# protestSignNode.net
KiCad netlist of a schematic drawn in EAGLE
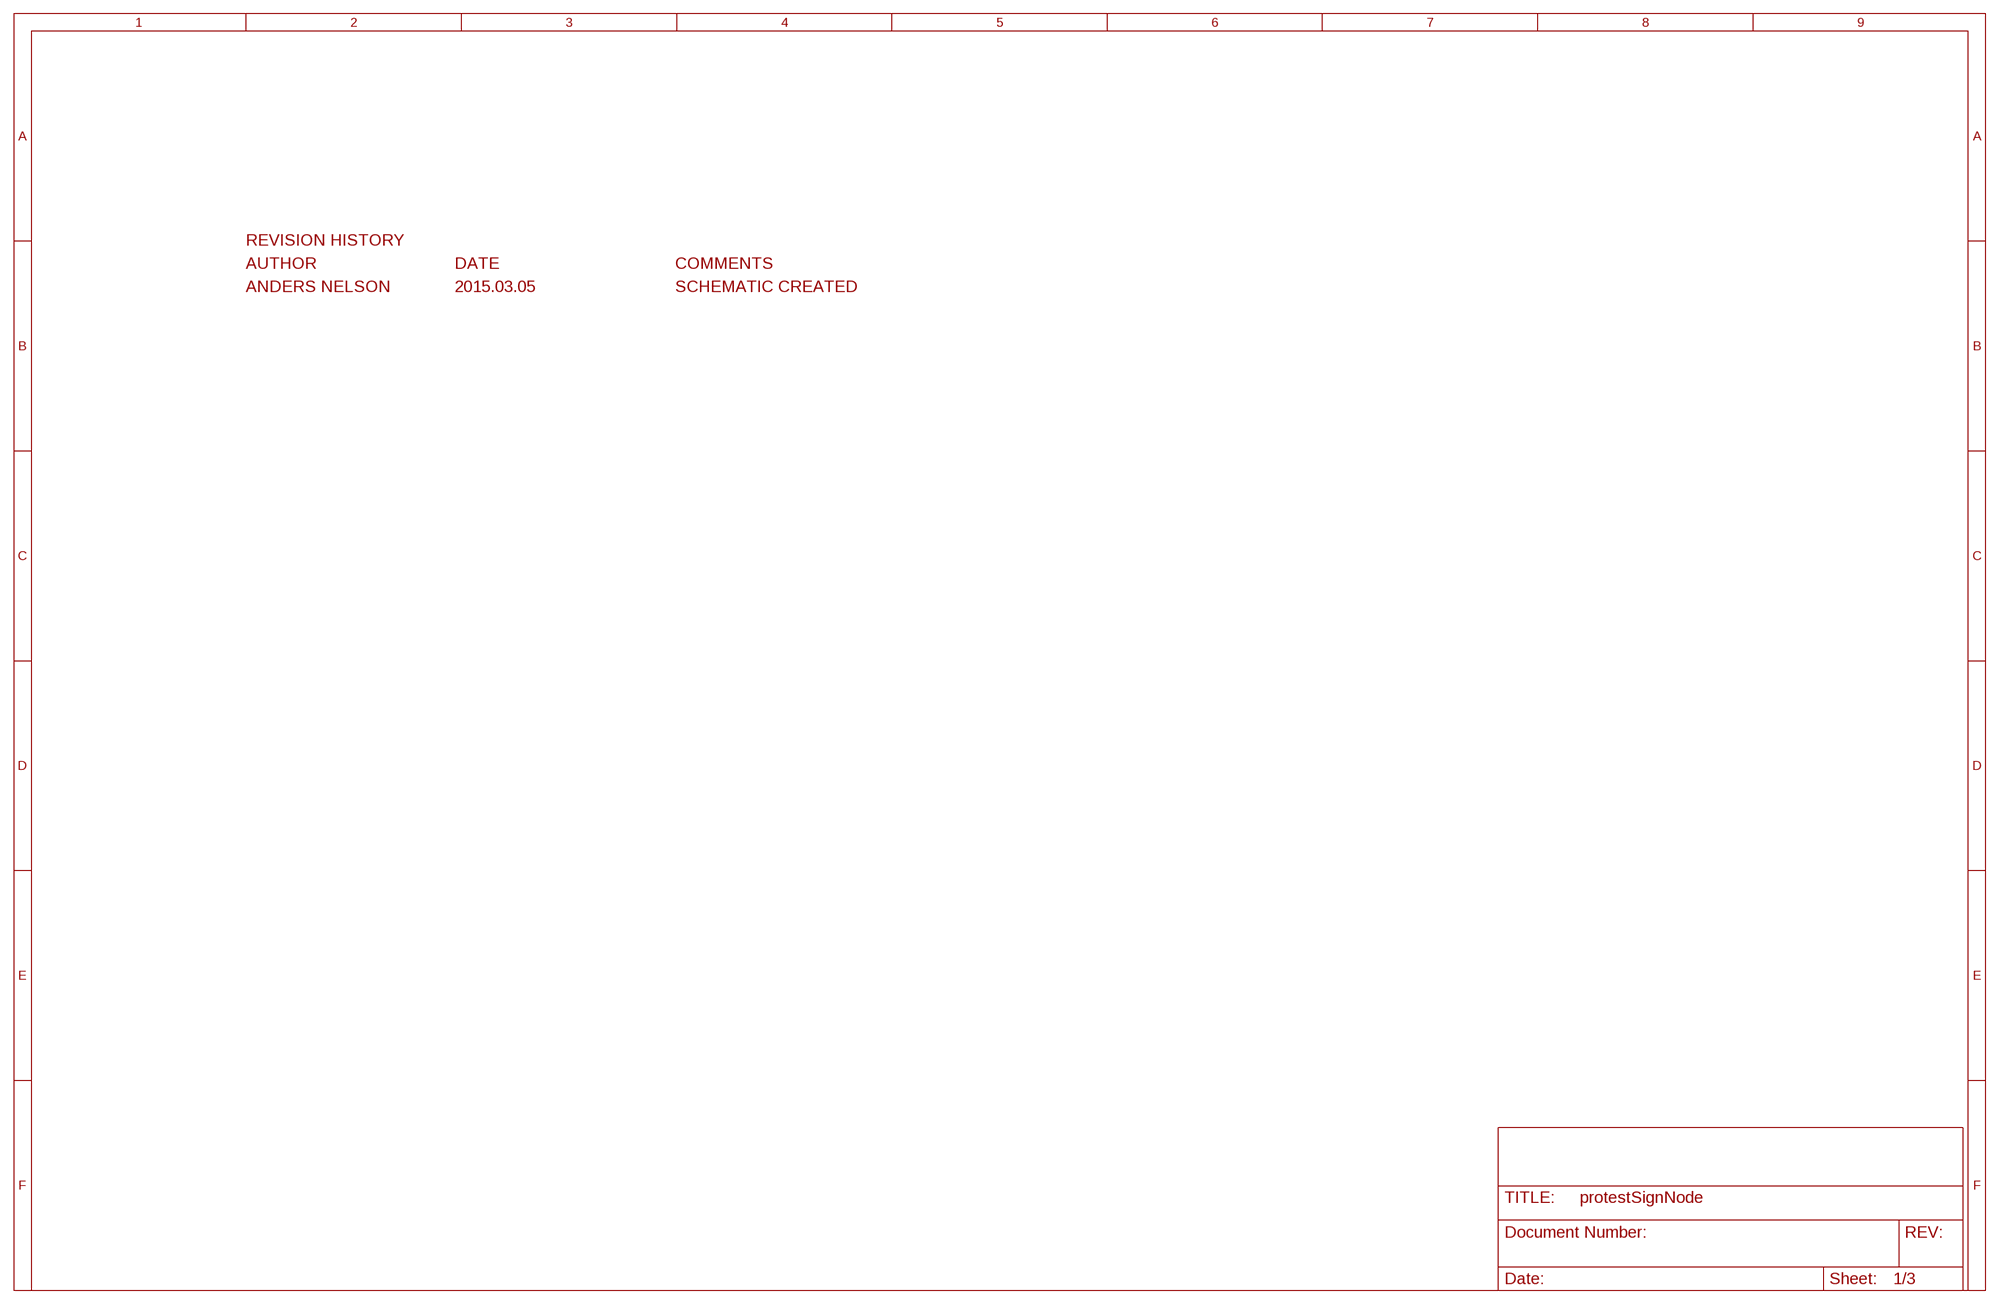
[diagram p0: schematic, sheet 1]
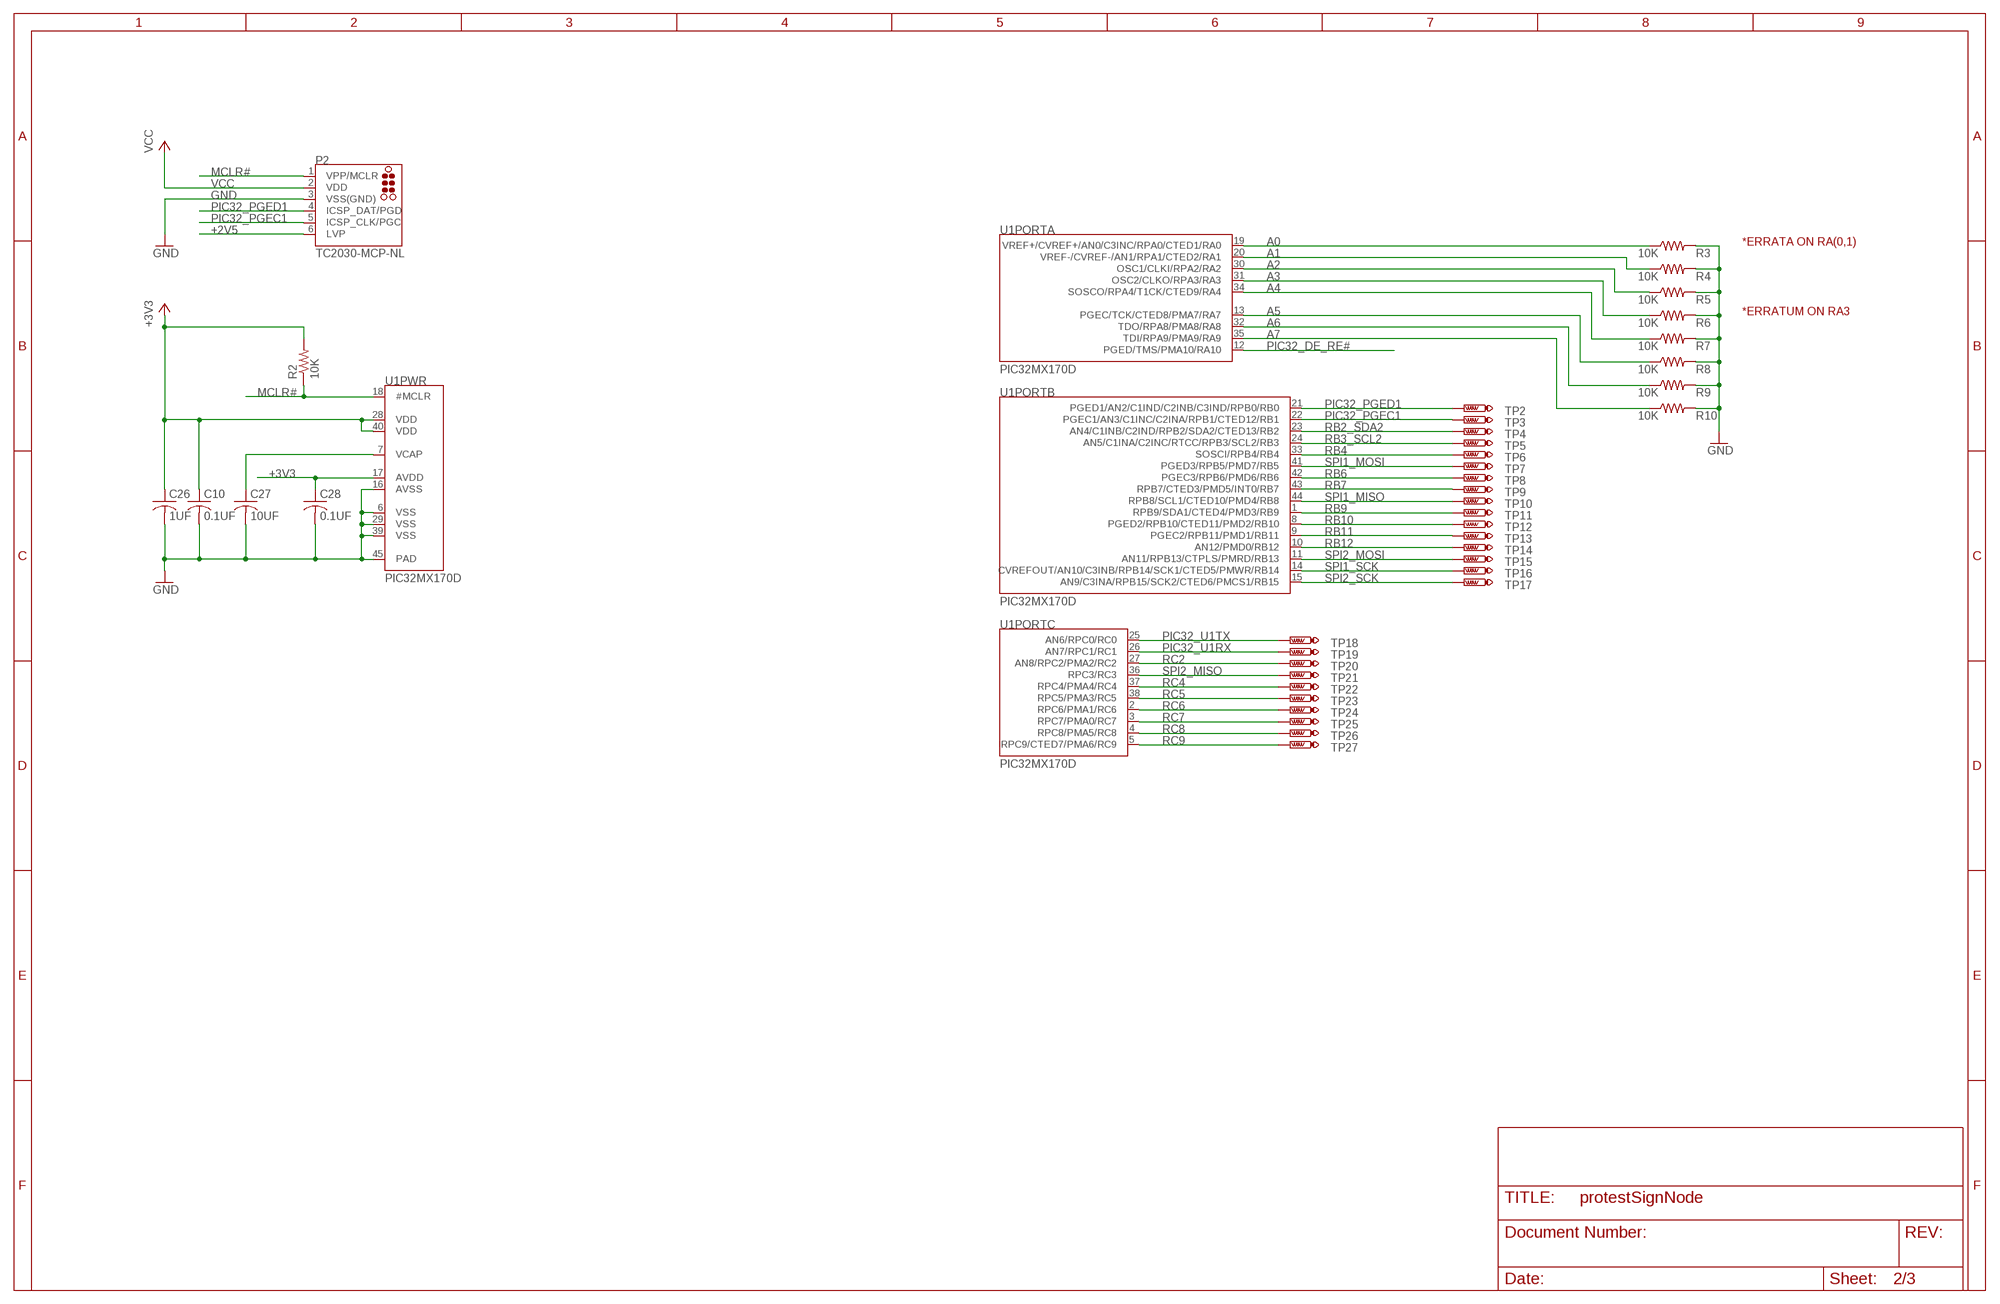
[diagram p1: schematic, sheet 2]
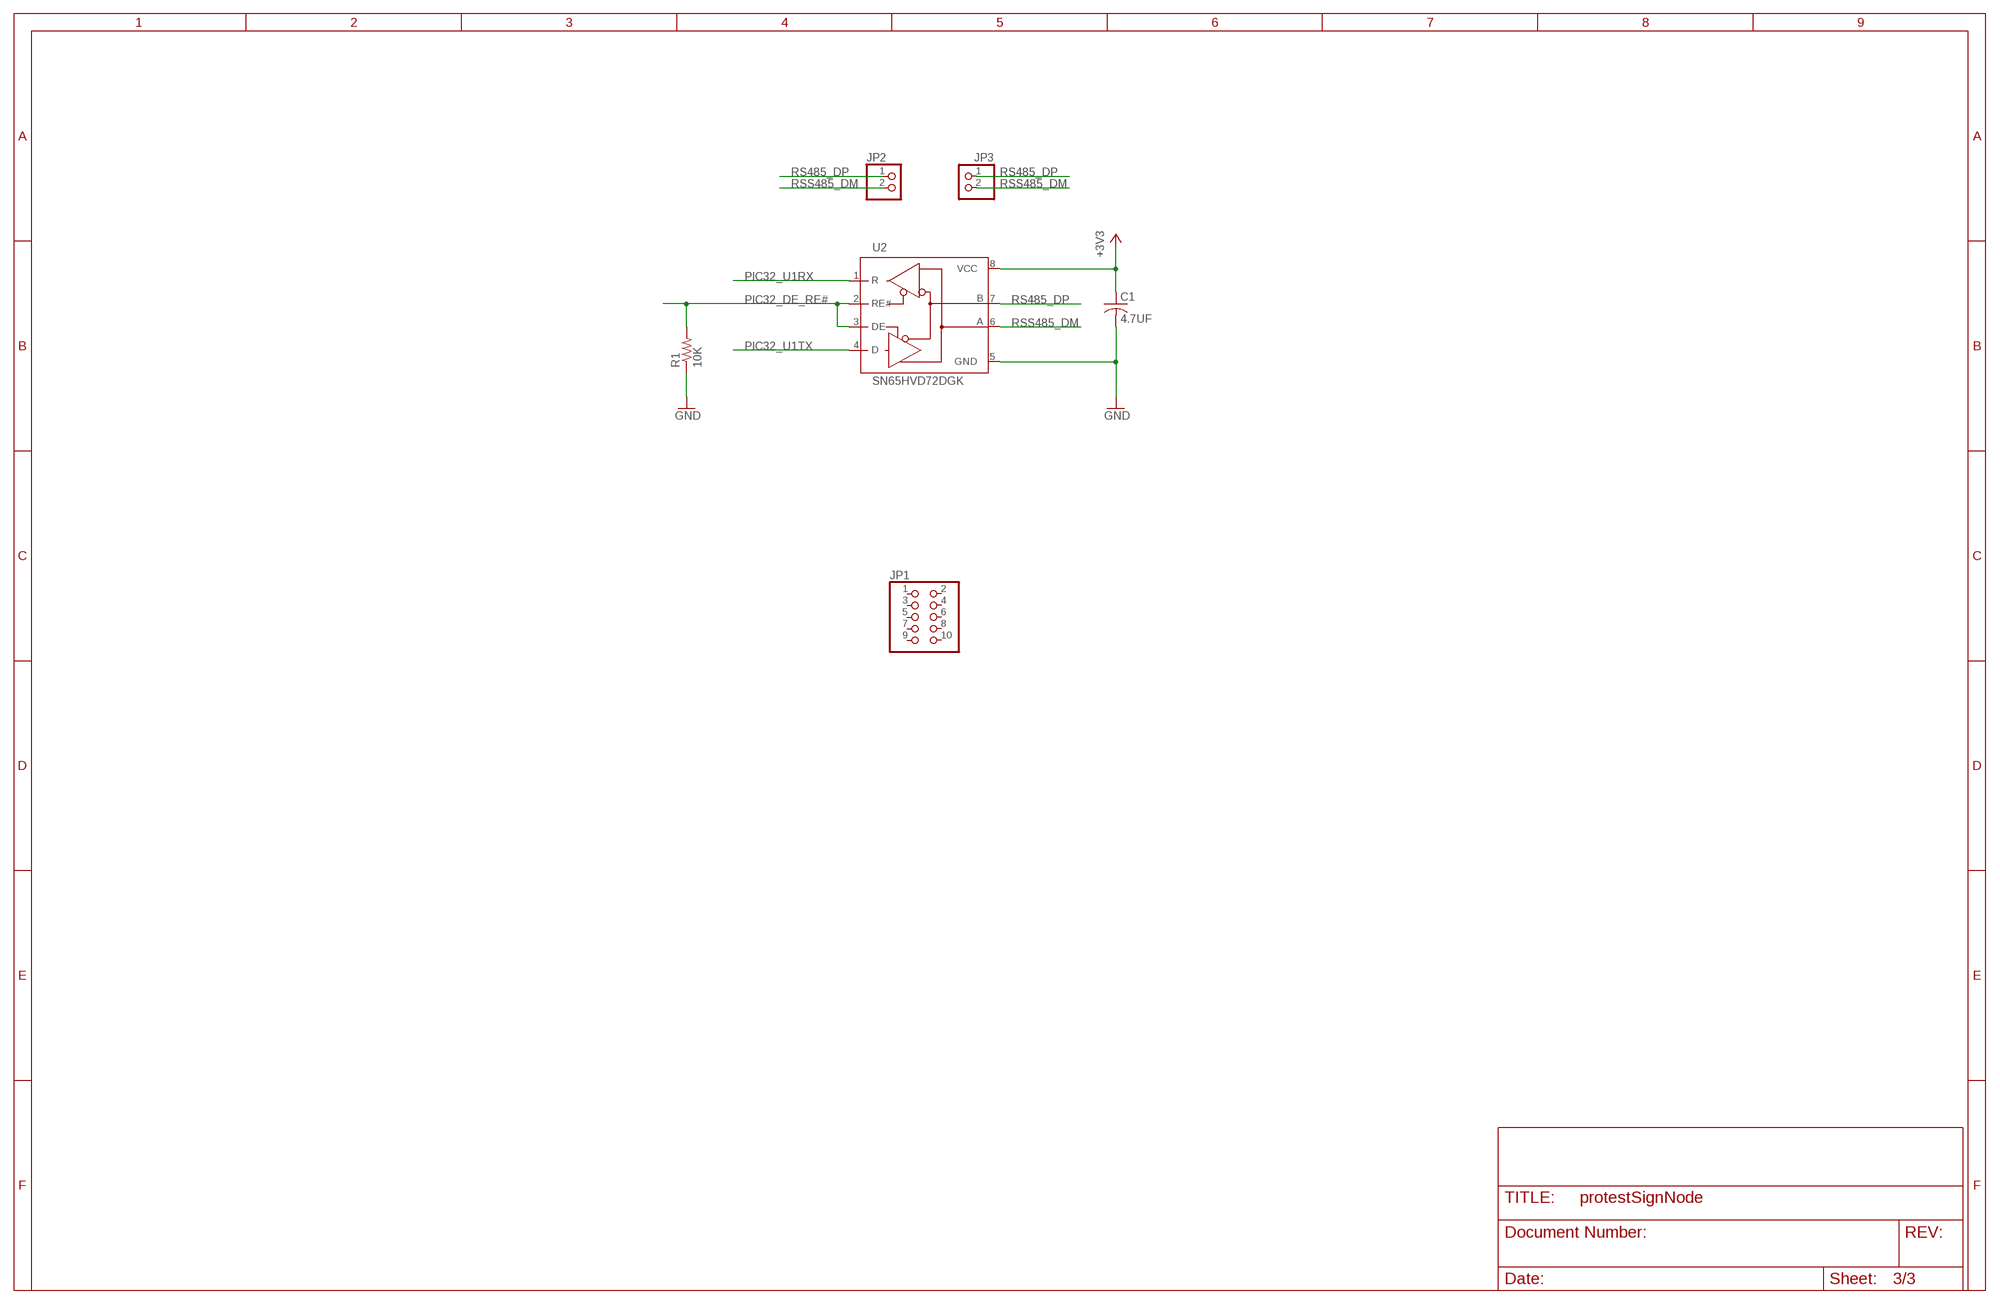
[diagram p2: schematic, sheet 3]

(export (version "E")
  (design (tool "Eeschema 10.0.6"))
  (components
    (comp (ref "C10")
      (value "0.1UF")
      (footprint "eagle-import:C0402")
      (libsource (lib "eagle-import") (part "C-USC0402"))
    )
    (comp (ref "C26")
      (value "1UF")
      (footprint "eagle-import:C0402")
      (libsource (lib "eagle-import") (part "C-USC0402"))
    )
    (comp (ref "C27")
      (value "10UF")
      (footprint "eagle-import:C0603")
      (libsource (lib "eagle-import") (part "C-USC0603"))
    )
    (comp (ref "C28")
      (value "0.1UF")
      (footprint "eagle-import:C0402")
      (libsource (lib "eagle-import") (part "C-USC0402"))
    )
    (comp (ref "P2")
      (value "TC2030-MCP-NL")
      (footprint "eagle-import:TC2030-MCP-NL")
      (libsource (lib "eagle-import") (part "TC2030-MCP-NL"))
    )
    (comp (ref "R2")
      (value "10K")
      (footprint "eagle-import:R0402")
      (libsource (lib "eagle-import") (part "R-US_R0402"))
    )
    (comp (ref "R3")
      (value "10K")
      (footprint "eagle-import:R0402")
      (libsource (lib "eagle-import") (part "R-US_R0402"))
    )
    (comp (ref "R4")
      (value "10K")
      (footprint "eagle-import:R0402")
      (libsource (lib "eagle-import") (part "R-US_R0402"))
    )
    (comp (ref "R5")
      (value "10K")
      (footprint "eagle-import:R0402")
      (libsource (lib "eagle-import") (part "R-US_R0402"))
    )
    (comp (ref "R6")
      (value "10K")
      (footprint "eagle-import:R0402")
      (libsource (lib "eagle-import") (part "R-US_R0402"))
    )
    (comp (ref "R7")
      (value "10K")
      (footprint "eagle-import:R0402")
      (libsource (lib "eagle-import") (part "R-US_R0402"))
    )
    (comp (ref "R8")
      (value "10K")
      (footprint "eagle-import:R0402")
      (libsource (lib "eagle-import") (part "R-US_R0402"))
    )
    (comp (ref "R9")
      (value "10K")
      (footprint "eagle-import:R0402")
      (libsource (lib "eagle-import") (part "R-US_R0402"))
    )
    (comp (ref "R10")
      (value "10K")
      (footprint "eagle-import:R0402")
      (libsource (lib "eagle-import") (part "R-US_R0402"))
    )
    (comp (ref "TP2")
      (value "PTR1B1,27")
      (footprint "eagle-import:B1,27")
      (libsource (lib "eagle-import") (part "PTR1B1,27"))
    )
    (comp (ref "TP3")
      (value "PTR1B1,27")
      (footprint "eagle-import:B1,27")
      (libsource (lib "eagle-import") (part "PTR1B1,27"))
    )
    (comp (ref "TP4")
      (value "PTR1B1,27")
      (footprint "eagle-import:B1,27")
      (libsource (lib "eagle-import") (part "PTR1B1,27"))
    )
    (comp (ref "TP5")
      (value "PTR1B1,27")
      (footprint "eagle-import:B1,27")
      (libsource (lib "eagle-import") (part "PTR1B1,27"))
    )
    (comp (ref "TP6")
      (value "PTR1B1,27")
      (footprint "eagle-import:B1,27")
      (libsource (lib "eagle-import") (part "PTR1B1,27"))
    )
    (comp (ref "TP7")
      (value "PTR1B1,27")
      (footprint "eagle-import:B1,27")
      (libsource (lib "eagle-import") (part "PTR1B1,27"))
    )
    (comp (ref "TP8")
      (value "PTR1B1,27")
      (footprint "eagle-import:B1,27")
      (libsource (lib "eagle-import") (part "PTR1B1,27"))
    )
    (comp (ref "TP9")
      (value "PTR1B1,27")
      (footprint "eagle-import:B1,27")
      (libsource (lib "eagle-import") (part "PTR1B1,27"))
    )
    (comp (ref "TP10")
      (value "PTR1B1,27")
      (footprint "eagle-import:B1,27")
      (libsource (lib "eagle-import") (part "PTR1B1,27"))
    )
    (comp (ref "TP11")
      (value "PTR1B1,27")
      (footprint "eagle-import:B1,27")
      (libsource (lib "eagle-import") (part "PTR1B1,27"))
    )
    (comp (ref "TP12")
      (value "PTR1B1,27")
      (footprint "eagle-import:B1,27")
      (libsource (lib "eagle-import") (part "PTR1B1,27"))
    )
    (comp (ref "TP13")
      (value "PTR1B1,27")
      (footprint "eagle-import:B1,27")
      (libsource (lib "eagle-import") (part "PTR1B1,27"))
    )
    (comp (ref "TP14")
      (value "PTR1B1,27")
      (footprint "eagle-import:B1,27")
      (libsource (lib "eagle-import") (part "PTR1B1,27"))
    )
    (comp (ref "TP15")
      (value "PTR1B1,27")
      (footprint "eagle-import:B1,27")
      (libsource (lib "eagle-import") (part "PTR1B1,27"))
    )
    (comp (ref "TP16")
      (value "PTR1B1,27")
      (footprint "eagle-import:B1,27")
      (libsource (lib "eagle-import") (part "PTR1B1,27"))
    )
    (comp (ref "TP17")
      (value "PTR1B1,27")
      (footprint "eagle-import:B1,27")
      (libsource (lib "eagle-import") (part "PTR1B1,27"))
    )
    (comp (ref "TP18")
      (value "PTR1B1,27")
      (footprint "eagle-import:B1,27")
      (libsource (lib "eagle-import") (part "PTR1B1,27"))
    )
    (comp (ref "TP19")
      (value "PTR1B1,27")
      (footprint "eagle-import:B1,27")
      (libsource (lib "eagle-import") (part "PTR1B1,27"))
    )
    (comp (ref "TP20")
      (value "PTR1B1,27")
      (footprint "eagle-import:B1,27")
      (libsource (lib "eagle-import") (part "PTR1B1,27"))
    )
    (comp (ref "TP21")
      (value "PTR1B1,27")
      (footprint "eagle-import:B1,27")
      (libsource (lib "eagle-import") (part "PTR1B1,27"))
    )
    (comp (ref "TP22")
      (value "PTR1B1,27")
      (footprint "eagle-import:B1,27")
      (libsource (lib "eagle-import") (part "PTR1B1,27"))
    )
    (comp (ref "TP23")
      (value "PTR1B1,27")
      (footprint "eagle-import:B1,27")
      (libsource (lib "eagle-import") (part "PTR1B1,27"))
    )
    (comp (ref "TP24")
      (value "PTR1B1,27")
      (footprint "eagle-import:B1,27")
      (libsource (lib "eagle-import") (part "PTR1B1,27"))
    )
    (comp (ref "TP25")
      (value "PTR1B1,27")
      (footprint "eagle-import:B1,27")
      (libsource (lib "eagle-import") (part "PTR1B1,27"))
    )
    (comp (ref "TP26")
      (value "PTR1B1,27")
      (footprint "eagle-import:B1,27")
      (libsource (lib "eagle-import") (part "PTR1B1,27"))
    )
    (comp (ref "TP27")
      (value "PTR1B1,27")
      (footprint "eagle-import:B1,27")
      (libsource (lib "eagle-import") (part "PTR1B1,27"))
    )
    (comp (ref "U1")
      (value "PIC32MX170D")
      (footprint "eagle-import:VTLA44")
      (libsource (lib "eagle-import") (part "PIC32MX1D70"))
    )
    (comp (ref "C1")
      (value "4.7UF")
      (footprint "eagle-import:C0603")
      (libsource (lib "eagle-import") (part "C-USC0603"))
    )
    (comp (ref "JP1")
      (value "PINHD-2X5")
      (footprint "eagle-import:2X05")
      (libsource (lib "eagle-import") (part "PINHD-2X5"))
    )
    (comp (ref "JP2")
      (value "PINHD-1X2/90")
      (footprint "eagle-import:1X02_90")
      (libsource (lib "eagle-import") (part "PINHD-1X2/90"))
    )
    (comp (ref "JP3")
      (value "PINHD-1X2/90")
      (footprint "eagle-import:1X02_90")
      (libsource (lib "eagle-import") (part "PINHD-1X2/90"))
    )
    (comp (ref "R1")
      (value "10K")
      (footprint "eagle-import:R0402")
      (libsource (lib "eagle-import") (part "R-US_R0402"))
    )
    (comp (ref "U2")
      (value "SN65HVD72DGK")
      (footprint "eagle-import:DGK")
      (libsource (lib "eagle-import") (part "SN65HVD7DGK2"))
    )
  )
  (nets
    (net (code "1") (name "+2V5") (class "Default")
      (node (ref "P2") (pin "6") (pinfunction "LVP_6") (pintype "bidirectional"))
    )
    (net (code "2") (name "+3V3") (class "Default")
      (node (ref "C1") (pin "1") (pinfunction "1_1") (pintype "passive"))
      (node (ref "C10") (pin "1") (pinfunction "1_1") (pintype "passive"))
      (node (ref "C26") (pin "1") (pinfunction "1_1") (pintype "passive"))
      (node (ref "C28") (pin "1") (pinfunction "1_1") (pintype "passive"))
      (node (ref "R2") (pin "2") (pinfunction "2_2") (pintype "passive"))
      (node (ref "U1") (pin "17") (pinfunction "AVDD_17") (pintype "bidirectional"))
      (node (ref "U1") (pin "28") (pinfunction "VDD_28") (pintype "bidirectional"))
      (node (ref "U1") (pin "40") (pinfunction "VDD_40") (pintype "bidirectional"))
      (node (ref "U2") (pin "8") (pinfunction "VCC_8") (pintype "power_in"))
    )
    (net (code "3") (name "A0") (class "Default")
      (node (ref "R3") (pin "1") (pinfunction "1_1") (pintype "passive"))
      (node (ref "U1") (pin "19") (pinfunction "VREF+/CVREF+/AN0/C3INC/RPA0/CTED1/RA0_19") (pintype "bidirectional"))
    )
    (net (code "4") (name "A1") (class "Default")
      (node (ref "R4") (pin "1") (pinfunction "1_1") (pintype "passive"))
      (node (ref "U1") (pin "20") (pinfunction "VREF-/CVREF-/AN1/RPA1/CTED2/RA1_20") (pintype "bidirectional"))
    )
    (net (code "5") (name "A2") (class "Default")
      (node (ref "R5") (pin "1") (pinfunction "1_1") (pintype "passive"))
      (node (ref "U1") (pin "30") (pinfunction "OSC1/CLKI/RPA2/RA2_30") (pintype "bidirectional"))
    )
    (net (code "6") (name "A3") (class "Default")
      (node (ref "R6") (pin "1") (pinfunction "1_1") (pintype "passive"))
      (node (ref "U1") (pin "31") (pinfunction "OSC2/CLKO/RPA3/RA3_31") (pintype "bidirectional"))
    )
    (net (code "7") (name "A4") (class "Default")
      (node (ref "R7") (pin "1") (pinfunction "1_1") (pintype "passive"))
      (node (ref "U1") (pin "34") (pinfunction "SOSCO/RPA4/T1CK/CTED9/RA4_34") (pintype "bidirectional"))
    )
    (net (code "8") (name "A5") (class "Default")
      (node (ref "R8") (pin "1") (pinfunction "1_1") (pintype "passive"))
      (node (ref "U1") (pin "13") (pinfunction "PGEC/TCK/CTED8/PMA7/RA7_13") (pintype "bidirectional"))
    )
    (net (code "9") (name "A6") (class "Default")
      (node (ref "R9") (pin "1") (pinfunction "1_1") (pintype "passive"))
      (node (ref "U1") (pin "32") (pinfunction "TDO/RPA8/PMA8/RA8_32") (pintype "bidirectional"))
    )
    (net (code "10") (name "A7") (class "Default")
      (node (ref "R10") (pin "1") (pinfunction "1_1") (pintype "passive"))
      (node (ref "U1") (pin "35") (pinfunction "TDI/RPA9/PMA9/RA9_35") (pintype "bidirectional"))
    )
    (net (code "11") (name "GND") (class "Default")
      (node (ref "C1") (pin "2") (pinfunction "2_2") (pintype "passive"))
      (node (ref "C10") (pin "2") (pinfunction "2_2") (pintype "passive"))
      (node (ref "C26") (pin "2") (pinfunction "2_2") (pintype "passive"))
      (node (ref "C27") (pin "2") (pinfunction "2_2") (pintype "passive"))
      (node (ref "C28") (pin "2") (pinfunction "2_2") (pintype "passive"))
      (node (ref "P2") (pin "3") (pinfunction "VSS(GND)_3") (pintype "power_in"))
      (node (ref "R1") (pin "1") (pinfunction "1_1") (pintype "passive"))
      (node (ref "R10") (pin "2") (pinfunction "2_2") (pintype "passive"))
      (node (ref "R3") (pin "2") (pinfunction "2_2") (pintype "passive"))
      (node (ref "R4") (pin "2") (pinfunction "2_2") (pintype "passive"))
      (node (ref "R5") (pin "2") (pinfunction "2_2") (pintype "passive"))
      (node (ref "R6") (pin "2") (pinfunction "2_2") (pintype "passive"))
      (node (ref "R7") (pin "2") (pinfunction "2_2") (pintype "passive"))
      (node (ref "R8") (pin "2") (pinfunction "2_2") (pintype "passive"))
      (node (ref "R9") (pin "2") (pinfunction "2_2") (pintype "passive"))
      (node (ref "U1") (pin "16") (pinfunction "AVSS_16") (pintype "bidirectional"))
      (node (ref "U1") (pin "29") (pinfunction "VSS_29") (pintype "bidirectional"))
      (node (ref "U1") (pin "39") (pinfunction "VSS_39") (pintype "bidirectional"))
      (node (ref "U1") (pin "45") (pinfunction "PAD_45") (pintype "bidirectional"))
      (node (ref "U1") (pin "6") (pinfunction "VSS_6") (pintype "bidirectional"))
      (node (ref "U2") (pin "5") (pinfunction "GND_5") (pintype "power_in"))
    )
    (net (code "12") (name "MCLR#") (class "Default")
      (node (ref "P2") (pin "1") (pinfunction "VPP/MCLR_1") (pintype "passive"))
      (node (ref "R2") (pin "1") (pinfunction "1_1") (pintype "passive"))
      (node (ref "U1") (pin "18") (pinfunction "#MCLR_18") (pintype "bidirectional"))
    )
    (net (code "13") (name "Net-(U1D-VCAP)") (class "Default")
      (node (ref "C27") (pin "1") (pinfunction "1_1") (pintype "passive"))
      (node (ref "U1") (pin "7") (pinfunction "VCAP_7") (pintype "bidirectional"))
    )
    (net (code "14") (name "PIC32_DE_RE#") (class "Default")
      (node (ref "R1") (pin "2") (pinfunction "2_2") (pintype "passive"))
      (node (ref "U1") (pin "12") (pinfunction "PGED/TMS/PMA10/RA10_12") (pintype "bidirectional"))
      (node (ref "U2") (pin "2") (pinfunction "RE#_2") (pintype "input"))
      (node (ref "U2") (pin "3") (pinfunction "DE_3") (pintype "input"))
    )
    (net (code "15") (name "PIC32_PGEC1") (class "Default")
      (node (ref "P2") (pin "5") (pinfunction "ICSP_CLK/PGC_5") (pintype "output"))
      (node (ref "TP3") (pin "TP") (pinfunction "TP_TP") (pintype "input"))
      (node (ref "U1") (pin "22") (pinfunction "PGEC1/AN3/C1INC/C2INA/RPB1/CTED12/RB1_22") (pintype "bidirectional"))
    )
    (net (code "16") (name "PIC32_PGED1") (class "Default")
      (node (ref "P2") (pin "4") (pinfunction "ICSP_DAT/PGD_4") (pintype "bidirectional"))
      (node (ref "TP2") (pin "TP") (pinfunction "TP_TP") (pintype "input"))
      (node (ref "U1") (pin "21") (pinfunction "PGED1/AN2/C1IND/C2INB/C3IND/RPB0/RB0_21") (pintype "bidirectional"))
    )
    (net (code "17") (name "PIC32_U1RX") (class "Default")
      (node (ref "TP19") (pin "TP") (pinfunction "TP_TP") (pintype "input"))
      (node (ref "U1") (pin "26") (pinfunction "AN7/RPC1/RC1_26") (pintype "bidirectional"))
      (node (ref "U2") (pin "1") (pinfunction "R_1") (pintype "output"))
    )
    (net (code "18") (name "PIC32_U1TX") (class "Default")
      (node (ref "TP18") (pin "TP") (pinfunction "TP_TP") (pintype "input"))
      (node (ref "U1") (pin "25") (pinfunction "AN6/RPC0/RC0_25") (pintype "bidirectional"))
      (node (ref "U2") (pin "4") (pinfunction "D_4") (pintype "input"))
    )
    (net (code "19") (name "RB2_SDA2") (class "Default")
      (node (ref "TP4") (pin "TP") (pinfunction "TP_TP") (pintype "input"))
      (node (ref "U1") (pin "23") (pinfunction "AN4/C1INB/C2IND/RPB2/SDA2/CTED13/RB2_23") (pintype "bidirectional"))
    )
    (net (code "20") (name "RB3_SCL2") (class "Default")
      (node (ref "TP5") (pin "TP") (pinfunction "TP_TP") (pintype "input"))
      (node (ref "U1") (pin "24") (pinfunction "AN5/C1INA/C2INC/RTCC/RPB3/SCL2/RB3_24") (pintype "bidirectional"))
    )
    (net (code "21") (name "RB4") (class "Default")
      (node (ref "TP6") (pin "TP") (pinfunction "TP_TP") (pintype "input"))
      (node (ref "U1") (pin "33") (pinfunction "SOSCI/RPB4/RB4_33") (pintype "bidirectional"))
    )
    (net (code "22") (name "RB6") (class "Default")
      (node (ref "TP8") (pin "TP") (pinfunction "TP_TP") (pintype "input"))
      (node (ref "U1") (pin "42") (pinfunction "PGEC3/RPB6/PMD6/RB6_42") (pintype "bidirectional"))
    )
    (net (code "23") (name "RB7") (class "Default")
      (node (ref "TP9") (pin "TP") (pinfunction "TP_TP") (pintype "input"))
      (node (ref "U1") (pin "43") (pinfunction "RPB7/CTED3/PMD5/INT0/RB7_43") (pintype "bidirectional"))
    )
    (net (code "24") (name "RB9") (class "Default")
      (node (ref "TP11") (pin "TP") (pinfunction "TP_TP") (pintype "input"))
      (node (ref "U1") (pin "1") (pinfunction "RPB9/SDA1/CTED4/PMD3/RB9_1") (pintype "bidirectional"))
    )
    (net (code "25") (name "RB10") (class "Default")
      (node (ref "TP12") (pin "TP") (pinfunction "TP_TP") (pintype "input"))
      (node (ref "U1") (pin "8") (pinfunction "PGED2/RPB10/CTED11/PMD2/RB10_8") (pintype "bidirectional"))
    )
    (net (code "26") (name "RB11") (class "Default")
      (node (ref "TP13") (pin "TP") (pinfunction "TP_TP") (pintype "input"))
      (node (ref "U1") (pin "9") (pinfunction "PGEC2/RPB11/PMD1/RB11_9") (pintype "bidirectional"))
    )
    (net (code "27") (name "RB12") (class "Default")
      (node (ref "TP14") (pin "TP") (pinfunction "TP_TP") (pintype "input"))
      (node (ref "U1") (pin "10") (pinfunction "AN12/PMD0/RB12_10") (pintype "bidirectional"))
    )
    (net (code "28") (name "RC2") (class "Default")
      (node (ref "TP20") (pin "TP") (pinfunction "TP_TP") (pintype "input"))
      (node (ref "U1") (pin "27") (pinfunction "AN8/RPC2/PMA2/RC2_27") (pintype "bidirectional"))
    )
    (net (code "29") (name "RC4") (class "Default")
      (node (ref "TP22") (pin "TP") (pinfunction "TP_TP") (pintype "input"))
      (node (ref "U1") (pin "37") (pinfunction "RPC4/PMA4/RC4_37") (pintype "bidirectional"))
    )
    (net (code "30") (name "RC5") (class "Default")
      (node (ref "TP23") (pin "TP") (pinfunction "TP_TP") (pintype "input"))
      (node (ref "U1") (pin "38") (pinfunction "RPC5/PMA3/RC5_38") (pintype "bidirectional"))
    )
    (net (code "31") (name "RC6") (class "Default")
      (node (ref "TP24") (pin "TP") (pinfunction "TP_TP") (pintype "input"))
      (node (ref "U1") (pin "2") (pinfunction "RPC6/PMA1/RC6_2") (pintype "bidirectional"))
    )
    (net (code "32") (name "RC7") (class "Default")
      (node (ref "TP25") (pin "TP") (pinfunction "TP_TP") (pintype "input"))
      (node (ref "U1") (pin "3") (pinfunction "RPC7/PMA0/RC7_3") (pintype "bidirectional"))
    )
    (net (code "33") (name "RC8") (class "Default")
      (node (ref "TP26") (pin "TP") (pinfunction "TP_TP") (pintype "input"))
      (node (ref "U1") (pin "4") (pinfunction "RPC8/PMA5/RC8_4") (pintype "bidirectional"))
    )
    (net (code "34") (name "RC9") (class "Default")
      (node (ref "TP27") (pin "TP") (pinfunction "TP_TP") (pintype "input"))
      (node (ref "U1") (pin "5") (pinfunction "RPC9/CTED7/PMA6/RC9_5") (pintype "bidirectional"))
    )
    (net (code "35") (name "RS485_DP") (class "Default")
      (node (ref "JP2") (pin "1") (pinfunction "1_1") (pintype "passive"))
      (node (ref "JP3") (pin "1") (pinfunction "1_1") (pintype "passive"))
      (node (ref "U2") (pin "7") (pinfunction "B_7") (pintype "passive"))
    )
    (net (code "36") (name "RSS485_DM") (class "Default")
      (node (ref "JP2") (pin "2") (pinfunction "2_2") (pintype "passive"))
      (node (ref "JP3") (pin "2") (pinfunction "2_2") (pintype "passive"))
      (node (ref "U2") (pin "6") (pinfunction "A_6") (pintype "passive"))
    )
    (net (code "37") (name "SPI1_MISO") (class "Default")
      (node (ref "TP10") (pin "TP") (pinfunction "TP_TP") (pintype "input"))
      (node (ref "U1") (pin "44") (pinfunction "RPB8/SCL1/CTED10/PMD4/RB8_44") (pintype "bidirectional"))
    )
    (net (code "38") (name "SPI1_MOSI") (class "Default")
      (node (ref "TP7") (pin "TP") (pinfunction "TP_TP") (pintype "input"))
      (node (ref "U1") (pin "41") (pinfunction "PGED3/RPB5/PMD7/RB5_41") (pintype "bidirectional"))
    )
    (net (code "39") (name "SPI1_SCK") (class "Default")
      (node (ref "TP16") (pin "TP") (pinfunction "TP_TP") (pintype "input"))
      (node (ref "U1") (pin "14") (pinfunction "CVREFOUT/AN10/C3INB/RPB14/SCK1/CTED5/PMWR/RB14_14") (pintype "bidirectional"))
    )
    (net (code "40") (name "SPI2_MISO") (class "Default")
      (node (ref "TP21") (pin "TP") (pinfunction "TP_TP") (pintype "input"))
      (node (ref "U1") (pin "36") (pinfunction "RPC3/RC3_36") (pintype "bidirectional"))
    )
    (net (code "41") (name "SPI2_MOSI") (class "Default")
      (node (ref "TP15") (pin "TP") (pinfunction "TP_TP") (pintype "input"))
      (node (ref "U1") (pin "11") (pinfunction "AN11/RPB13/CTPLS/PMRD/RB13_11") (pintype "bidirectional"))
    )
    (net (code "42") (name "SPI2_SCK") (class "Default")
      (node (ref "TP17") (pin "TP") (pinfunction "TP_TP") (pintype "input"))
      (node (ref "U1") (pin "15") (pinfunction "AN9/C3INA/RPB15/SCK2/CTED6/PMCS1/RB15_15") (pintype "bidirectional"))
    )
    (net (code "43") (name "VCC") (class "Default")
      (node (ref "P2") (pin "2") (pinfunction "VDD_2") (pintype "power_in"))
    )
    (net (code "44") (name "unconnected-(JP1-Pad1)") (class "Default")
      (node (ref "JP1") (pin "1") (pinfunction "1_1") (pintype "passive"))
    )
    (net (code "45") (name "unconnected-(JP1-Pad2)") (class "Default")
      (node (ref "JP1") (pin "2") (pinfunction "2_2") (pintype "passive"))
    )
    (net (code "46") (name "unconnected-(JP1-Pad3)") (class "Default")
      (node (ref "JP1") (pin "3") (pinfunction "3_3") (pintype "passive"))
    )
    (net (code "47") (name "unconnected-(JP1-Pad4)") (class "Default")
      (node (ref "JP1") (pin "4") (pinfunction "4_4") (pintype "passive"))
    )
    (net (code "48") (name "unconnected-(JP1-Pad5)") (class "Default")
      (node (ref "JP1") (pin "5") (pinfunction "5_5") (pintype "passive"))
    )
    (net (code "49") (name "unconnected-(JP1-Pad6)") (class "Default")
      (node (ref "JP1") (pin "6") (pinfunction "6_6") (pintype "passive"))
    )
    (net (code "50") (name "unconnected-(JP1-Pad7)") (class "Default")
      (node (ref "JP1") (pin "7") (pinfunction "7_7") (pintype "passive"))
    )
    (net (code "51") (name "unconnected-(JP1-Pad8)") (class "Default")
      (node (ref "JP1") (pin "8") (pinfunction "8_8") (pintype "passive"))
    )
    (net (code "52") (name "unconnected-(JP1-Pad9)") (class "Default")
      (node (ref "JP1") (pin "9") (pinfunction "9_9") (pintype "passive"))
    )
    (net (code "53") (name "unconnected-(JP1-Pad10)") (class "Default")
      (node (ref "JP1") (pin "10") (pinfunction "10_10") (pintype "passive"))
    )
  )
)
